# koosh_sensor_top_lighthouse.net
KiCad netlist of a schematic drawn in Altium Designer
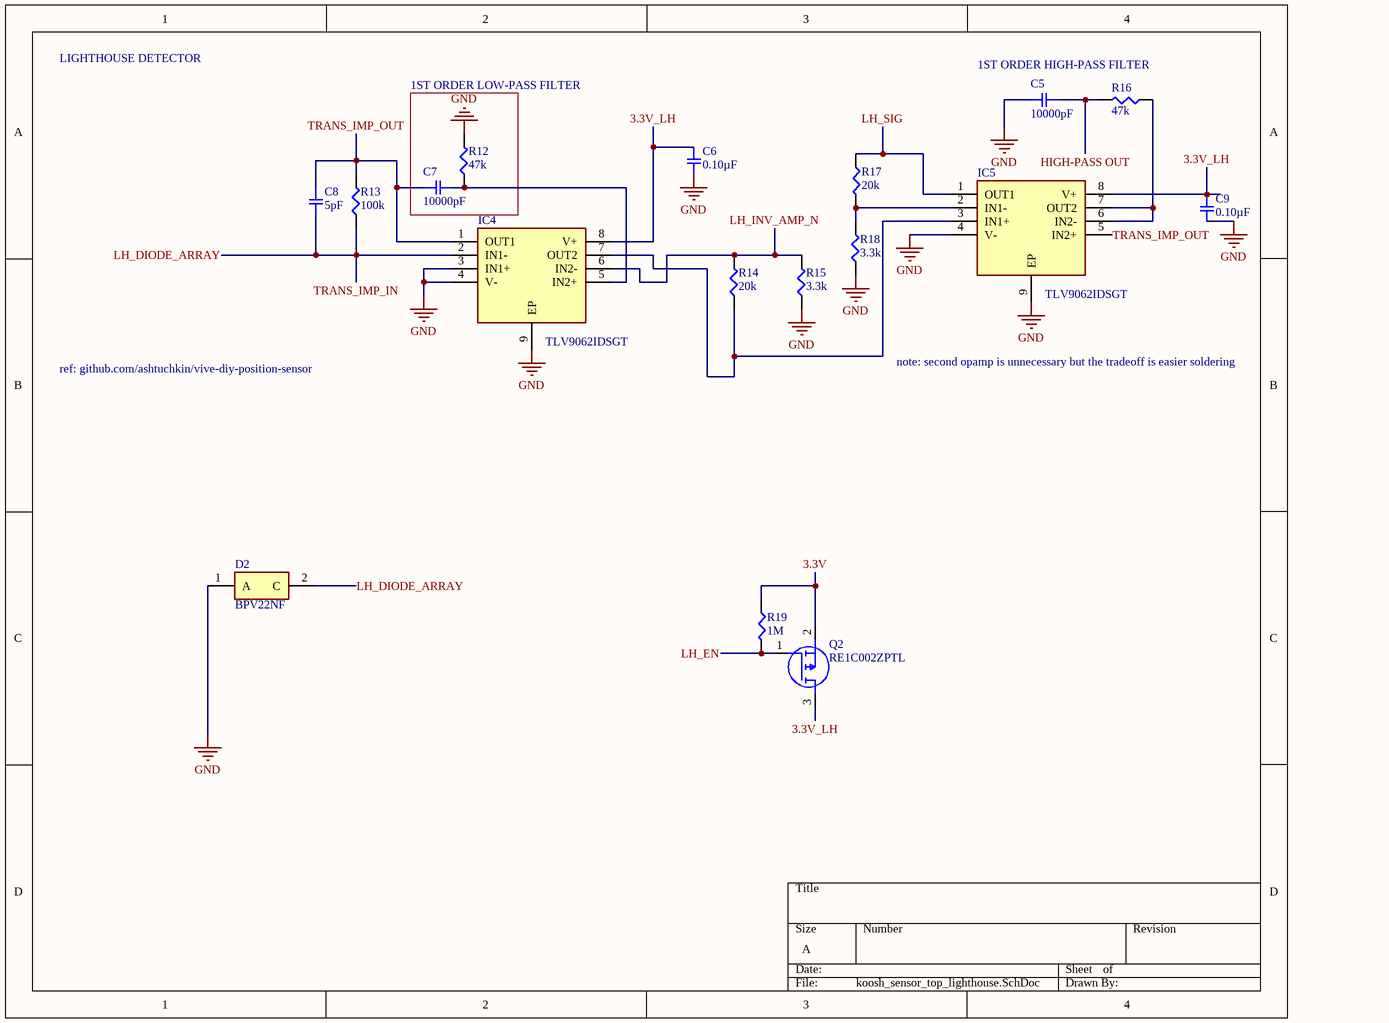
[diagram p0: koosh_sensor_top_lighthouse.SchDoc]

(export (version "E")
  (design (tool "Eeschema 10.0.6"))
  (components
    (comp (ref "C5")
      (value "10000pF")
      (footprint "SMD-0402C")
      (description "CAP CER 10000PF 50V X7R 0402")
      (fields
        (field (name "DIGI-KEY PART NUMBER") "490-4762-1-ND")
        (field (name "PART NUMBER") "GCM155R71H103KA55D")
      )
      (libsource (lib "capacitor_murata_0402") (part "GCM155R71H103KA55D"))
    )
    (comp (ref "C6")
      (value "0.10µF")
      (footprint "SMD-0402C")
      (description "CAP CER 0.1UF 16V X7R 0402")
      (fields
        (field (name "DIGI-KEY PART NUMBER") "490-4759-1-ND")
        (field (name "PART NUMBER") "GCM155R71C104KA55D")
      )
      (libsource (lib "capacitor_murata_0402") (part "GCM155R71C104KA55D"))
    )
    (comp (ref "C7")
      (value "10000pF")
      (footprint "SMD-0402C")
      (description "CAP CER 10000PF 50V X7R 0402")
      (fields
        (field (name "DIGI-KEY PART NUMBER") "490-4762-1-ND")
        (field (name "PART NUMBER") "GCM155R71H103KA55D")
      )
      (libsource (lib "capacitor_murata_0402") (part "GCM155R71H103KA55D"))
    )
    (comp (ref "C8")
      (value "5pF")
      (footprint "SMD-0402C")
      (description "CAP CER 5PF 50V NP0 0402")
      (fields
        (field (name "DIGI-KEY PART NUMBER") "490-8103-1-ND")
        (field (name "PART NUMBER") "GJM1555C1H5R0BB01D")
      )
      (libsource (lib "capacitor_murata_0402") (part "GJM1555C1H5R0BB01D"))
    )
    (comp (ref "C9")
      (value "0.10µF")
      (footprint "SMD-0402C")
      (description "CAP CER 0.1UF 16V X7R 0402")
      (fields
        (field (name "DIGI-KEY PART NUMBER") "490-4759-1-ND")
        (field (name "PART NUMBER") "GCM155R71C104KA55D")
      )
      (libsource (lib "capacitor_murata_0402") (part "GCM155R71C104KA55D"))
    )
    (comp (ref "D2")
      (value "BPV22NF")
      (footprint "SamacSys:TO254P510X450X920-2P")
      (description "Diode")
      (fields (field (name "MOUSER PART NUMBER") "782-BPV22NF") (field (name "RS PART NUMBER") "6997604P"))
      (libsource (lib "*") (part "BPV22NF"))
    )
    (comp (ref "IC4")
      (value "TLV9062IDSGT")
      (footprint "SON50P200X200X80-9N")
      (description "Integrated Circuit")
      (fields (field (name "MOUSER PART NUMBER") "595-TLV9062IDSGT"))
      (libsource (lib "SamacSys") (part "TLV9062IDSGT"))
    )
    (comp (ref "IC5")
      (value "TLV9062IDSGT")
      (footprint "SamacSys:SON50P200X200X80-9N")
      (description "Integrated Circuit")
      (fields (field (name "MOUSER PART NUMBER") "595-TLV9062IDSGT"))
      (libsource (lib "SamacSys") (part "TLV9062IDSGT"))
    )
    (comp (ref "Q2")
      (value "RE1C002ZPTL")
      (footprint "SamacSys:SOTFL50P160X85-3N")
      (description "MOSFET (P-Channel)")
      (fields
        (field (name "MOUSER PART NUMBER") "755-RE1C002ZPTL")
        (field (name "RS PART NUMBER") "1486960P")
      )
      (libsource (lib "*") (part "RE1C002ZPTL"))
    )
    (comp (ref "R12")
      (value "47k")
      (footprint "SMD-0402-RES")
      (description "RES SMD 47K OHM 5% 1/10W 0402")
      (fields (field (name "PART NUMBER") "ERJ-2GEJ473X") (field (name "DIGI-KEY PART NUMBER") "P47KJCT-ND"))
      (libsource (lib "Panasonic_ERJ_0402") (part "ERJ-2GEJ473X"))
    )
    (comp (ref "R13")
      (value "100k")
      (footprint "SMD-0402-RES")
      (description "RES SMD 100K OHM 5% 1/10W 0402")
      (fields (field (name "PART NUMBER") "ERJ-2GEJ104X") (field (name "DIGI-KEY PART NUMBER") "P100KJCT-ND"))
      (libsource (lib "Panasonic_ERJ_0402") (part "ERJ-2GEJ104X"))
    )
    (comp (ref "R14")
      (value "20k")
      (footprint "SMD-0402-RES")
      (description "RES SMD 20K OHM 5% 1/10W 0402")
      (fields (field (name "PART NUMBER") "ERJ-2GEJ473X") (field (name "DIGI-KEY PART NUMBER") "P47KJCT-ND"))
      (libsource (lib "Panasonic_ERJ_0402") (part "ERJ-2GEJ473X"))
    )
    (comp (ref "R15")
      (value "3.3k")
      (footprint "SMD-0402-RES")
      (description "RES SMD 3.3K OHM 5% 1/10W 0402")
      (fields (field (name "PART NUMBER") "ERJ-2GEJ332X") (field (name "DIGI-KEY PART NUMBER") "P3.3KJCT-ND"))
      (libsource (lib "Panasonic_ERJ_0402") (part "ERJ-2GEJ332X"))
    )
    (comp (ref "R16")
      (value "47k")
      (footprint "SMD-0402-RES")
      (description "RES SMD 47K OHM 5% 1/10W 0402")
      (fields (field (name "PART NUMBER") "ERJ-2GEJ473X") (field (name "DIGI-KEY PART NUMBER") "P47KJCT-ND"))
      (libsource (lib "Panasonic_ERJ_0402") (part "ERJ-2GEJ473X"))
    )
    (comp (ref "R17")
      (value "20k")
      (footprint "SMD-0402-RES")
      (description "RES SMD 20K OHM 5% 1/10W 0402")
      (fields (field (name "PART NUMBER") "ERJ-2GEJ473X") (field (name "DIGI-KEY PART NUMBER") "P47KJCT-ND"))
      (libsource (lib "Panasonic_ERJ_0402") (part "ERJ-2GEJ473X"))
    )
    (comp (ref "R18")
      (value "3.3k")
      (footprint "SMD-0402-RES")
      (description "RES SMD 3.3K OHM 5% 1/10W 0402")
      (fields (field (name "PART NUMBER") "ERJ-2GEJ332X") (field (name "DIGI-KEY PART NUMBER") "P3.3KJCT-ND"))
      (libsource (lib "Panasonic_ERJ_0402") (part "ERJ-2GEJ332X"))
    )
    (comp (ref "R19")
      (value "1M")
      (footprint "SMD-0402-RES")
      (description "RES SMD 1M OHM 5% 1/10W 0402")
      (fields (field (name "PART NUMBER") "ERJ-2GEJ105X") (field (name "DIGI-KEY PART NUMBER") "P1.0MJCT-ND"))
      (libsource (lib "Panasonic_ERJ_0402") (part "ERJ-2GEJ105X"))
    )
  )
  (nets
    (net (code "1") (name "/3.3V") (class "Default")
      (node (ref "Q2") (pin "2") (pinfunction "S_2") (pintype "passive"))
      (node (ref "R19") (pin "1") (pinfunction "1_1") (pintype "passive"))
    )
    (net (code "2") (name "/3.3V_LH") (class "Default")
      (node (ref "C6") (pin "1") (pinfunction "1_1") (pintype "passive"))
      (node (ref "C9") (pin "1") (pinfunction "1_1") (pintype "passive"))
      (node (ref "IC4") (pin "8") (pinfunction "V+_8") (pintype "passive"))
      (node (ref "IC5") (pin "8") (pinfunction "V+_8") (pintype "passive"))
      (node (ref "Q2") (pin "3") (pinfunction "D_3") (pintype "passive"))
    )
    (net (code "3") (name "/HIGH-PASS OUT") (class "Default")
      (node (ref "C5") (pin "1") (pinfunction "1_1") (pintype "passive"))
      (node (ref "R16") (pin "2") (pinfunction "2_2") (pintype "passive"))
    )
    (net (code "4") (name "/LH_DIODE_ARRAY") (class "Default")
      (node (ref "C8") (pin "2") (pinfunction "2_2") (pintype "passive"))
      (node (ref "D2") (pin "2") (pinfunction "C_2") (pintype "passive"))
      (node (ref "IC4") (pin "2") (pinfunction "IN1-_2") (pintype "passive"))
      (node (ref "R13") (pin "1") (pinfunction "1_1") (pintype "passive"))
    )
    (net (code "5") (name "/LH_EN") (class "Default")
      (node (ref "Q2") (pin "1") (pinfunction "G_1") (pintype "passive"))
      (node (ref "R19") (pin "2") (pinfunction "2_2") (pintype "passive"))
    )
    (net (code "6") (name "/LH_INV_AMP_N") (class "Default")
      (node (ref "IC4") (pin "6") (pinfunction "IN2-_6") (pintype "passive"))
      (node (ref "R14") (pin "2") (pinfunction "2_2") (pintype "passive"))
      (node (ref "R15") (pin "2") (pinfunction "2_2") (pintype "passive"))
    )
    (net (code "7") (name "/LH_SIG") (class "Default")
      (node (ref "IC5") (pin "1") (pinfunction "OUT1_1") (pintype "passive"))
      (node (ref "R17") (pin "1") (pinfunction "1_1") (pintype "passive"))
    )
    (net (code "8") (name "/TRANS_IMP_OUT") (class "Default")
      (node (ref "C7") (pin "1") (pinfunction "1_1") (pintype "passive"))
      (node (ref "C8") (pin "1") (pinfunction "1_1") (pintype "passive"))
      (node (ref "IC4") (pin "1") (pinfunction "OUT1_1") (pintype "passive"))
      (node (ref "IC5") (pin "5") (pinfunction "IN2+_5") (pintype "passive"))
      (node (ref "R13") (pin "2") (pinfunction "2_2") (pintype "passive"))
    )
    (net (code "9") (name "GND") (class "Default")
      (node (ref "C5") (pin "2") (pinfunction "2_2") (pintype "passive"))
      (node (ref "C6") (pin "2") (pinfunction "2_2") (pintype "passive"))
      (node (ref "C9") (pin "2") (pinfunction "2_2") (pintype "passive"))
      (node (ref "D2") (pin "1") (pinfunction "A_1") (pintype "passive"))
      (node (ref "IC4") (pin "3") (pinfunction "IN1+_3") (pintype "passive"))
      (node (ref "IC4") (pin "4") (pinfunction "V-_4") (pintype "passive"))
      (node (ref "IC4") (pin "9") (pinfunction "EP_9") (pintype "passive"))
      (node (ref "IC5") (pin "4") (pinfunction "V-_4") (pintype "passive"))
      (node (ref "IC5") (pin "9") (pinfunction "EP_9") (pintype "passive"))
      (node (ref "R12") (pin "2") (pinfunction "2_2") (pintype "passive"))
      (node (ref "R15") (pin "1") (pinfunction "1_1") (pintype "passive"))
      (node (ref "R18") (pin "1") (pinfunction "1_1") (pintype "passive"))
    )
    (net (code "10") (name "Net-(IC4-IN2+)") (class "Default")
      (node (ref "C7") (pin "2") (pinfunction "2_2") (pintype "passive"))
      (node (ref "IC4") (pin "5") (pinfunction "IN2+_5") (pintype "passive"))
      (node (ref "R12") (pin "1") (pinfunction "1_1") (pintype "passive"))
    )
    (net (code "11") (name "Net-(IC4-OUT2)") (class "Default")
      (node (ref "IC4") (pin "7") (pinfunction "OUT2_7") (pintype "passive"))
      (node (ref "IC5") (pin "3") (pinfunction "IN1+_3") (pintype "passive"))
      (node (ref "R14") (pin "1") (pinfunction "1_1") (pintype "passive"))
    )
    (net (code "12") (name "Net-(IC5-IN1-)") (class "Default")
      (node (ref "IC5") (pin "2") (pinfunction "IN1-_2") (pintype "passive"))
      (node (ref "R17") (pin "2") (pinfunction "2_2") (pintype "passive"))
      (node (ref "R18") (pin "2") (pinfunction "2_2") (pintype "passive"))
    )
    (net (code "13") (name "Net-(IC5-IN2-)") (class "Default")
      (node (ref "IC5") (pin "6") (pinfunction "IN2-_6") (pintype "passive"))
      (node (ref "IC5") (pin "7") (pinfunction "OUT2_7") (pintype "passive"))
      (node (ref "R16") (pin "1") (pinfunction "1_1") (pintype "passive"))
    )
  )
)
